# FPGA_Bank_3.net
KiCad netlist of a schematic drawn in Altium Designer
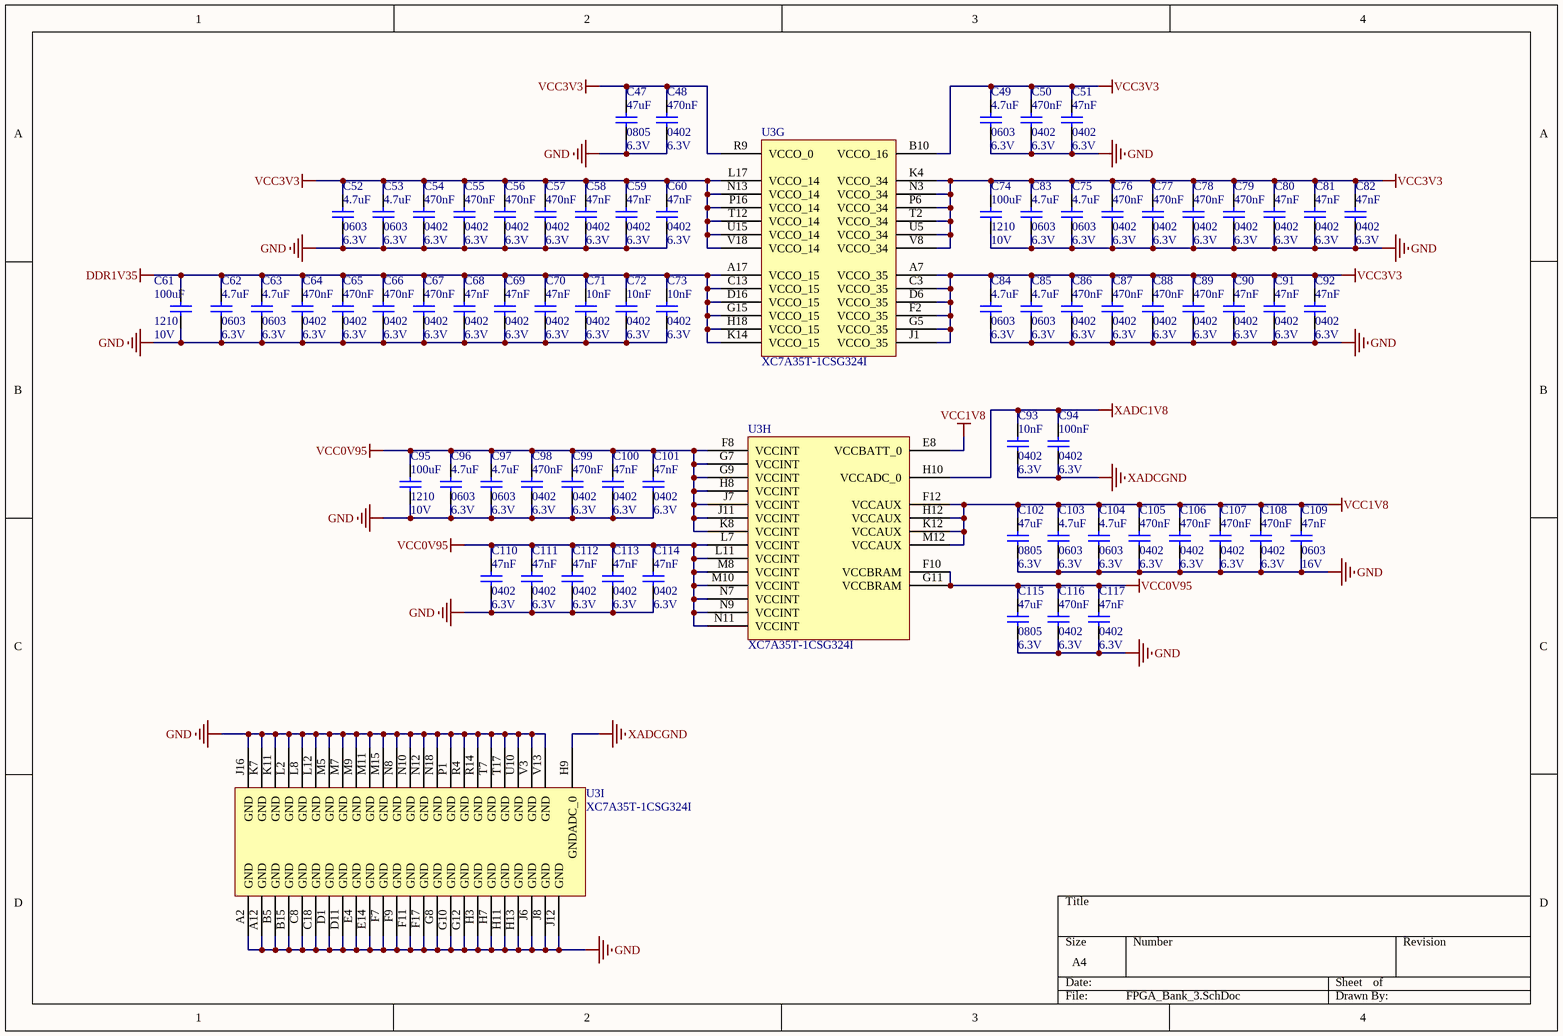
[diagram p0: FPGA_Bank_3.SchDoc]

(export (version "E")
  (design (tool "Eeschema 10.0.6"))
  (components
    (comp (ref "C47")
      (value "47uF")
      (footprint "2012[0805]")
      (description "Capacitor (Semiconductor SIM Model)")
      (fields
        (field (name "PACKAGEREFERENCE") "0805")
        (field (name "V") "6.3V")
        (field (name "PUBLISHER") "Altium Limited")
      )
      (libsource (lib "Devices") (part "Cap Semi"))
    )
    (comp (ref "C48")
      (value "470nF")
      (footprint "0402")
      (description "Capacitor (Semiconductor SIM Model)")
      (fields
        (field (name "PACKAGEREFERENCE") "0402")
        (field (name "V") "6.3V")
        (field (name "PUBLISHER") "Altium Limited")
      )
      (libsource (lib "Devices") (part "Cap Semi"))
    )
    (comp (ref "C49")
      (value "4.7uF")
      (footprint "1608[0603]")
      (description "Capacitor (Semiconductor SIM Model)")
      (fields
        (field (name "PACKAGEREFERENCE") "0603")
        (field (name "V") "6.3V")
        (field (name "PUBLISHER") "Altium Limited")
      )
      (libsource (lib "Devices") (part "Cap Semi"))
    )
    (comp (ref "C50")
      (value "470nF")
      (footprint "0402")
      (description "Capacitor (Semiconductor SIM Model)")
      (fields
        (field (name "PACKAGEREFERENCE") "0402")
        (field (name "V") "6.3V")
        (field (name "PUBLISHER") "Altium Limited")
      )
      (libsource (lib "Devices") (part "Cap Semi"))
    )
    (comp (ref "C51")
      (value "47nF")
      (footprint "0402")
      (description "Capacitor (Semiconductor SIM Model)")
      (fields
        (field (name "PACKAGEREFERENCE") "0402")
        (field (name "V") "6.3V")
        (field (name "PUBLISHER") "Altium Limited")
      )
      (libsource (lib "Devices") (part "Cap Semi"))
    )
    (comp (ref "C52")
      (value "4.7uF")
      (footprint "1608[0603]")
      (description "Capacitor (Semiconductor SIM Model)")
      (fields
        (field (name "PACKAGEREFERENCE") "0603")
        (field (name "V") "6.3V")
        (field (name "PUBLISHER") "Altium Limited")
      )
      (libsource (lib "Devices") (part "Cap Semi"))
    )
    (comp (ref "C53")
      (value "4.7uF")
      (footprint "1608[0603]")
      (description "Capacitor (Semiconductor SIM Model)")
      (fields
        (field (name "PACKAGEREFERENCE") "0603")
        (field (name "V") "6.3V")
        (field (name "PUBLISHER") "Altium Limited")
      )
      (libsource (lib "Devices") (part "Cap Semi"))
    )
    (comp (ref "C54")
      (value "470nF")
      (footprint "0402")
      (description "Capacitor (Semiconductor SIM Model)")
      (fields
        (field (name "PACKAGEREFERENCE") "0402")
        (field (name "V") "6.3V")
        (field (name "PUBLISHER") "Altium Limited")
      )
      (libsource (lib "Devices") (part "Cap Semi"))
    )
    (comp (ref "C55")
      (value "470nF")
      (footprint "0402")
      (description "Capacitor (Semiconductor SIM Model)")
      (fields
        (field (name "PACKAGEREFERENCE") "0402")
        (field (name "V") "6.3V")
        (field (name "PUBLISHER") "Altium Limited")
      )
      (libsource (lib "Devices") (part "Cap Semi"))
    )
    (comp (ref "C56")
      (value "470nF")
      (footprint "0402")
      (description "Capacitor (Semiconductor SIM Model)")
      (fields
        (field (name "PACKAGEREFERENCE") "0402")
        (field (name "V") "6.3V")
        (field (name "PUBLISHER") "Altium Limited")
      )
      (libsource (lib "Devices") (part "Cap Semi"))
    )
    (comp (ref "C57")
      (value "470nF")
      (footprint "0402")
      (description "Capacitor (Semiconductor SIM Model)")
      (fields
        (field (name "PACKAGEREFERENCE") "0402")
        (field (name "V") "6.3V")
        (field (name "PUBLISHER") "Altium Limited")
      )
      (libsource (lib "Devices") (part "Cap Semi"))
    )
    (comp (ref "C58")
      (value "47nF")
      (footprint "0402")
      (description "Capacitor (Semiconductor SIM Model)")
      (fields
        (field (name "PACKAGEREFERENCE") "0402")
        (field (name "V") "6.3V")
        (field (name "PUBLISHER") "Altium Limited")
      )
      (libsource (lib "Devices") (part "Cap Semi"))
    )
    (comp (ref "C59")
      (value "47nF")
      (footprint "0402")
      (description "Capacitor (Semiconductor SIM Model)")
      (fields
        (field (name "PACKAGEREFERENCE") "0402")
        (field (name "V") "6.3V")
        (field (name "PUBLISHER") "Altium Limited")
      )
      (libsource (lib "Devices") (part "Cap Semi"))
    )
    (comp (ref "C60")
      (value "47nF")
      (footprint "0402")
      (description "Capacitor (Semiconductor SIM Model)")
      (fields
        (field (name "PACKAGEREFERENCE") "0402")
        (field (name "V") "6.3V")
        (field (name "PUBLISHER") "Altium Limited")
      )
      (libsource (lib "Devices") (part "Cap Semi"))
    )
    (comp (ref "C61")
      (value "100uF")
      (footprint "2012[0805]")
      (description "Capacitor (Semiconductor SIM Model)")
      (fields
        (field (name "PACKAGEREFERENCE") "1210")
        (field (name "V") "10V")
        (field (name "PUBLISHER") "Altium Limited")
      )
      (libsource (lib "Devices") (part "Cap Semi"))
    )
    (comp (ref "C62")
      (value "4.7uF")
      (footprint "1608[0603]")
      (description "Capacitor (Semiconductor SIM Model)")
      (fields
        (field (name "PACKAGEREFERENCE") "0603")
        (field (name "V") "6.3V")
        (field (name "PUBLISHER") "Altium Limited")
      )
      (libsource (lib "Devices") (part "Cap Semi"))
    )
    (comp (ref "C63")
      (value "4.7uF")
      (footprint "1608[0603]")
      (description "Capacitor (Semiconductor SIM Model)")
      (fields
        (field (name "PACKAGEREFERENCE") "0603")
        (field (name "V") "6.3V")
        (field (name "PUBLISHER") "Altium Limited")
      )
      (libsource (lib "Devices") (part "Cap Semi"))
    )
    (comp (ref "C64")
      (value "470nF")
      (footprint "0402")
      (description "Capacitor (Semiconductor SIM Model)")
      (fields
        (field (name "PACKAGEREFERENCE") "0402")
        (field (name "V") "6.3V")
        (field (name "PUBLISHER") "Altium Limited")
      )
      (libsource (lib "Devices") (part "Cap Semi"))
    )
    (comp (ref "C65")
      (value "470nF")
      (footprint "0402")
      (description "Capacitor (Semiconductor SIM Model)")
      (fields
        (field (name "PACKAGEREFERENCE") "0402")
        (field (name "V") "6.3V")
        (field (name "PUBLISHER") "Altium Limited")
      )
      (libsource (lib "Devices") (part "Cap Semi"))
    )
    (comp (ref "C66")
      (value "470nF")
      (footprint "0402")
      (description "Capacitor (Semiconductor SIM Model)")
      (fields
        (field (name "PACKAGEREFERENCE") "0402")
        (field (name "V") "6.3V")
        (field (name "PUBLISHER") "Altium Limited")
      )
      (libsource (lib "Devices") (part "Cap Semi"))
    )
    (comp (ref "C67")
      (value "470nF")
      (footprint "0402")
      (description "Capacitor (Semiconductor SIM Model)")
      (fields
        (field (name "PACKAGEREFERENCE") "0402")
        (field (name "V") "6.3V")
        (field (name "PUBLISHER") "Altium Limited")
      )
      (libsource (lib "Devices") (part "Cap Semi"))
    )
    (comp (ref "C68")
      (value "47nF")
      (footprint "0402")
      (description "Capacitor (Semiconductor SIM Model)")
      (fields
        (field (name "PACKAGEREFERENCE") "0402")
        (field (name "V") "6.3V")
        (field (name "PUBLISHER") "Altium Limited")
      )
      (libsource (lib "Devices") (part "Cap Semi"))
    )
    (comp (ref "C69")
      (value "47nF")
      (footprint "0402")
      (description "Capacitor (Semiconductor SIM Model)")
      (fields
        (field (name "PACKAGEREFERENCE") "0402")
        (field (name "V") "6.3V")
        (field (name "PUBLISHER") "Altium Limited")
      )
      (libsource (lib "Devices") (part "Cap Semi"))
    )
    (comp (ref "C70")
      (value "47nF")
      (footprint "0402")
      (description "Capacitor (Semiconductor SIM Model)")
      (fields
        (field (name "PACKAGEREFERENCE") "0402")
        (field (name "V") "6.3V")
        (field (name "PUBLISHER") "Altium Limited")
      )
      (libsource (lib "Devices") (part "Cap Semi"))
    )
    (comp (ref "C71")
      (value "10nF")
      (footprint "0402")
      (description "Capacitor (Semiconductor SIM Model)")
      (fields
        (field (name "PACKAGEREFERENCE") "0402")
        (field (name "V") "6.3V")
        (field (name "PUBLISHER") "Altium Limited")
      )
      (libsource (lib "Devices") (part "Cap Semi"))
    )
    (comp (ref "C72")
      (value "10nF")
      (footprint "0402")
      (description "Capacitor (Semiconductor SIM Model)")
      (fields
        (field (name "PACKAGEREFERENCE") "0402")
        (field (name "V") "6.3V")
        (field (name "PUBLISHER") "Altium Limited")
      )
      (libsource (lib "Devices") (part "Cap Semi"))
    )
    (comp (ref "C73")
      (value "10nF")
      (footprint "0402")
      (description "Capacitor (Semiconductor SIM Model)")
      (fields
        (field (name "PACKAGEREFERENCE") "0402")
        (field (name "V") "6.3V")
        (field (name "PUBLISHER") "Altium Limited")
      )
      (libsource (lib "Devices") (part "Cap Semi"))
    )
    (comp (ref "C74")
      (value "100uF")
      (footprint "2012[0805]")
      (description "Capacitor (Semiconductor SIM Model)")
      (fields
        (field (name "PACKAGEREFERENCE") "1210")
        (field (name "V") "10V")
        (field (name "PUBLISHER") "Altium Limited")
      )
      (libsource (lib "Devices") (part "Cap Semi"))
    )
    (comp (ref "C75")
      (value "4.7uF")
      (footprint "1608[0603]")
      (description "Capacitor (Semiconductor SIM Model)")
      (fields
        (field (name "PACKAGEREFERENCE") "0603")
        (field (name "V") "6.3V")
        (field (name "PUBLISHER") "Altium Limited")
      )
      (libsource (lib "Devices") (part "Cap Semi"))
    )
    (comp (ref "C76")
      (value "470nF")
      (footprint "0402")
      (description "Capacitor (Semiconductor SIM Model)")
      (fields
        (field (name "PACKAGEREFERENCE") "0402")
        (field (name "V") "6.3V")
        (field (name "PUBLISHER") "Altium Limited")
      )
      (libsource (lib "Devices") (part "Cap Semi"))
    )
    (comp (ref "C77")
      (value "470nF")
      (footprint "0402")
      (description "Capacitor (Semiconductor SIM Model)")
      (fields
        (field (name "PACKAGEREFERENCE") "0402")
        (field (name "V") "6.3V")
        (field (name "PUBLISHER") "Altium Limited")
      )
      (libsource (lib "Devices") (part "Cap Semi"))
    )
    (comp (ref "C78")
      (value "470nF")
      (footprint "0402")
      (description "Capacitor (Semiconductor SIM Model)")
      (fields
        (field (name "PACKAGEREFERENCE") "0402")
        (field (name "V") "6.3V")
        (field (name "PUBLISHER") "Altium Limited")
      )
      (libsource (lib "Devices") (part "Cap Semi"))
    )
    (comp (ref "C79")
      (value "470nF")
      (footprint "0402")
      (description "Capacitor (Semiconductor SIM Model)")
      (fields
        (field (name "PACKAGEREFERENCE") "0402")
        (field (name "V") "6.3V")
        (field (name "PUBLISHER") "Altium Limited")
      )
      (libsource (lib "Devices") (part "Cap Semi"))
    )
    (comp (ref "C80")
      (value "47nF")
      (footprint "0402")
      (description "Capacitor (Semiconductor SIM Model)")
      (fields
        (field (name "PACKAGEREFERENCE") "0402")
        (field (name "V") "6.3V")
        (field (name "PUBLISHER") "Altium Limited")
      )
      (libsource (lib "Devices") (part "Cap Semi"))
    )
    (comp (ref "C81")
      (value "47nF")
      (footprint "0402")
      (description "Capacitor (Semiconductor SIM Model)")
      (fields
        (field (name "PACKAGEREFERENCE") "0402")
        (field (name "V") "6.3V")
        (field (name "PUBLISHER") "Altium Limited")
      )
      (libsource (lib "Devices") (part "Cap Semi"))
    )
    (comp (ref "C82")
      (value "47nF")
      (footprint "0402")
      (description "Capacitor (Semiconductor SIM Model)")
      (fields
        (field (name "PACKAGEREFERENCE") "0402")
        (field (name "V") "6.3V")
        (field (name "PUBLISHER") "Altium Limited")
      )
      (libsource (lib "Devices") (part "Cap Semi"))
    )
    (comp (ref "C83")
      (value "4.7uF")
      (footprint "1608[0603]")
      (description "Capacitor (Semiconductor SIM Model)")
      (fields
        (field (name "PACKAGEREFERENCE") "0603")
        (field (name "V") "6.3V")
        (field (name "PUBLISHER") "Altium Limited")
      )
      (libsource (lib "Devices") (part "Cap Semi"))
    )
    (comp (ref "C84")
      (value "4.7uF")
      (footprint "1608[0603]")
      (description "Capacitor (Semiconductor SIM Model)")
      (fields
        (field (name "PACKAGEREFERENCE") "0603")
        (field (name "V") "6.3V")
        (field (name "PUBLISHER") "Altium Limited")
      )
      (libsource (lib "Devices") (part "Cap Semi"))
    )
    (comp (ref "C85")
      (value "4.7uF")
      (footprint "1608[0603]")
      (description "Capacitor (Semiconductor SIM Model)")
      (fields
        (field (name "PACKAGEREFERENCE") "0603")
        (field (name "V") "6.3V")
        (field (name "PUBLISHER") "Altium Limited")
      )
      (libsource (lib "Devices") (part "Cap Semi"))
    )
    (comp (ref "C86")
      (value "470nF")
      (footprint "0402")
      (description "Capacitor (Semiconductor SIM Model)")
      (fields
        (field (name "PACKAGEREFERENCE") "0402")
        (field (name "V") "6.3V")
        (field (name "PUBLISHER") "Altium Limited")
      )
      (libsource (lib "Devices") (part "Cap Semi"))
    )
    (comp (ref "C87")
      (value "470nF")
      (footprint "0402")
      (description "Capacitor (Semiconductor SIM Model)")
      (fields
        (field (name "PACKAGEREFERENCE") "0402")
        (field (name "V") "6.3V")
        (field (name "PUBLISHER") "Altium Limited")
      )
      (libsource (lib "Devices") (part "Cap Semi"))
    )
    (comp (ref "C88")
      (value "470nF")
      (footprint "0402")
      (description "Capacitor (Semiconductor SIM Model)")
      (fields
        (field (name "PACKAGEREFERENCE") "0402")
        (field (name "V") "6.3V")
        (field (name "PUBLISHER") "Altium Limited")
      )
      (libsource (lib "Devices") (part "Cap Semi"))
    )
    (comp (ref "C89")
      (value "470nF")
      (footprint "0402")
      (description "Capacitor (Semiconductor SIM Model)")
      (fields
        (field (name "PACKAGEREFERENCE") "0402")
        (field (name "V") "6.3V")
        (field (name "PUBLISHER") "Altium Limited")
      )
      (libsource (lib "Devices") (part "Cap Semi"))
    )
    (comp (ref "C90")
      (value "47nF")
      (footprint "0402")
      (description "Capacitor (Semiconductor SIM Model)")
      (fields
        (field (name "PACKAGEREFERENCE") "0402")
        (field (name "V") "6.3V")
        (field (name "PUBLISHER") "Altium Limited")
      )
      (libsource (lib "Devices") (part "Cap Semi"))
    )
    (comp (ref "C91")
      (value "47nF")
      (footprint "0402")
      (description "Capacitor (Semiconductor SIM Model)")
      (fields
        (field (name "PACKAGEREFERENCE") "0402")
        (field (name "V") "6.3V")
        (field (name "PUBLISHER") "Altium Limited")
      )
      (libsource (lib "Devices") (part "Cap Semi"))
    )
    (comp (ref "C92")
      (value "47nF")
      (footprint "0402")
      (description "Capacitor (Semiconductor SIM Model)")
      (fields
        (field (name "PACKAGEREFERENCE") "0402")
        (field (name "V") "6.3V")
        (field (name "PUBLISHER") "Altium Limited")
      )
      (libsource (lib "Devices") (part "Cap Semi"))
    )
    (comp (ref "C93")
      (value "10nF")
      (footprint "0402")
      (description "Capacitor (Semiconductor SIM Model)")
      (fields
        (field (name "PACKAGEREFERENCE") "0402")
        (field (name "V") "6.3V")
        (field (name "PUBLISHER") "Altium Limited")
      )
      (libsource (lib "Devices") (part "Cap Semi"))
    )
    (comp (ref "C94")
      (value "100nF")
      (footprint "0402")
      (description "Capacitor (Semiconductor SIM Model)")
      (fields
        (field (name "PACKAGEREFERENCE") "0402")
        (field (name "V") "6.3V")
        (field (name "PUBLISHER") "Altium Limited")
      )
      (libsource (lib "Devices") (part "Cap Semi"))
    )
    (comp (ref "C95")
      (value "100uF")
      (footprint "2012[0805]")
      (description "Capacitor (Semiconductor SIM Model)")
      (fields
        (field (name "PACKAGEREFERENCE") "1210")
        (field (name "V") "10V")
        (field (name "PUBLISHER") "Altium Limited")
      )
      (libsource (lib "Devices") (part "Cap Semi"))
    )
    (comp (ref "C96")
      (value "4.7uF")
      (footprint "1608[0603]")
      (description "Capacitor (Semiconductor SIM Model)")
      (fields
        (field (name "PACKAGEREFERENCE") "0603")
        (field (name "V") "6.3V")
        (field (name "PUBLISHER") "Altium Limited")
      )
      (libsource (lib "Devices") (part "Cap Semi"))
    )
    (comp (ref "C97")
      (value "4.7uF")
      (footprint "1608[0603]")
      (description "Capacitor (Semiconductor SIM Model)")
      (fields
        (field (name "PACKAGEREFERENCE") "0603")
        (field (name "V") "6.3V")
        (field (name "PUBLISHER") "Altium Limited")
      )
      (libsource (lib "Devices") (part "Cap Semi"))
    )
    (comp (ref "C98")
      (value "470nF")
      (footprint "0402")
      (description "Capacitor (Semiconductor SIM Model)")
      (fields
        (field (name "PACKAGEREFERENCE") "0402")
        (field (name "V") "6.3V")
        (field (name "PUBLISHER") "Altium Limited")
      )
      (libsource (lib "Devices") (part "Cap Semi"))
    )
    (comp (ref "C99")
      (value "470nF")
      (footprint "0402")
      (description "Capacitor (Semiconductor SIM Model)")
      (fields
        (field (name "PACKAGEREFERENCE") "0402")
        (field (name "V") "6.3V")
        (field (name "PUBLISHER") "Altium Limited")
      )
      (libsource (lib "Devices") (part "Cap Semi"))
    )
    (comp (ref "C100")
      (value "47nF")
      (footprint "0402")
      (description "Capacitor (Semiconductor SIM Model)")
      (fields
        (field (name "PACKAGEREFERENCE") "0402")
        (field (name "V") "6.3V")
        (field (name "PUBLISHER") "Altium Limited")
      )
      (libsource (lib "Devices") (part "Cap Semi"))
    )
    (comp (ref "C101")
      (value "47nF")
      (footprint "0402")
      (description "Capacitor (Semiconductor SIM Model)")
      (fields
        (field (name "PACKAGEREFERENCE") "0402")
        (field (name "V") "6.3V")
        (field (name "PUBLISHER") "Altium Limited")
      )
      (libsource (lib "Devices") (part "Cap Semi"))
    )
    (comp (ref "C102")
      (value "47uF")
      (footprint "2012[0805]")
      (description "Capacitor (Semiconductor SIM Model)")
      (fields
        (field (name "PACKAGEREFERENCE") "0805")
        (field (name "V") "6.3V")
        (field (name "PUBLISHER") "Altium Limited")
      )
      (libsource (lib "Devices") (part "Cap Semi"))
    )
    (comp (ref "C103")
      (value "4.7uF")
      (footprint "1608[0603]")
      (description "Capacitor (Semiconductor SIM Model)")
      (fields
        (field (name "PACKAGEREFERENCE") "0603")
        (field (name "V") "6.3V")
        (field (name "PUBLISHER") "Altium Limited")
      )
      (libsource (lib "Devices") (part "Cap Semi"))
    )
    (comp (ref "C104")
      (value "4.7uF")
      (footprint "1608[0603]")
      (description "Capacitor (Semiconductor SIM Model)")
      (fields
        (field (name "PACKAGEREFERENCE") "0603")
        (field (name "V") "6.3V")
        (field (name "PUBLISHER") "Altium Limited")
      )
      (libsource (lib "Devices") (part "Cap Semi"))
    )
    (comp (ref "C105")
      (value "470nF")
      (footprint "0402")
      (description "Capacitor (Semiconductor SIM Model)")
      (fields
        (field (name "PACKAGEREFERENCE") "0402")
        (field (name "V") "6.3V")
        (field (name "PUBLISHER") "Altium Limited")
      )
      (libsource (lib "Devices") (part "Cap Semi"))
    )
    (comp (ref "C106")
      (value "470nF")
      (footprint "0402")
      (description "Capacitor (Semiconductor SIM Model)")
      (fields
        (field (name "PACKAGEREFERENCE") "0402")
        (field (name "V") "6.3V")
        (field (name "PUBLISHER") "Altium Limited")
      )
      (libsource (lib "Devices") (part "Cap Semi"))
    )
    (comp (ref "C107")
      (value "470nF")
      (footprint "0402")
      (description "Capacitor (Semiconductor SIM Model)")
      (fields
        (field (name "PACKAGEREFERENCE") "0402")
        (field (name "V") "6.3V")
        (field (name "PUBLISHER") "Altium Limited")
      )
      (libsource (lib "Devices") (part "Cap Semi"))
    )
    (comp (ref "C108")
      (value "470nF")
      (footprint "0402")
      (description "Capacitor (Semiconductor SIM Model)")
      (fields
        (field (name "PACKAGEREFERENCE") "0402")
        (field (name "V") "6.3V")
        (field (name "PUBLISHER") "Altium Limited")
      )
      (libsource (lib "Devices") (part "Cap Semi"))
    )
    (comp (ref "C109")
      (value "47nF")
      (footprint "1608[0603]")
      (description "Capacitor (Semiconductor SIM Model)")
      (fields
        (field (name "PACKAGEREFERENCE") "0603")
        (field (name "V") "16V")
        (field (name "PUBLISHER") "Altium Limited")
      )
      (libsource (lib "Devices") (part "Cap Semi"))
    )
    (comp (ref "C110")
      (value "47nF")
      (footprint "0402")
      (description "Capacitor (Semiconductor SIM Model)")
      (fields
        (field (name "PACKAGEREFERENCE") "0402")
        (field (name "V") "6.3V")
        (field (name "PUBLISHER") "Altium Limited")
      )
      (libsource (lib "Devices") (part "Cap Semi"))
    )
    (comp (ref "C111")
      (value "47nF")
      (footprint "0402")
      (description "Capacitor (Semiconductor SIM Model)")
      (fields
        (field (name "PACKAGEREFERENCE") "0402")
        (field (name "V") "6.3V")
        (field (name "PUBLISHER") "Altium Limited")
      )
      (libsource (lib "Devices") (part "Cap Semi"))
    )
    (comp (ref "C112")
      (value "47nF")
      (footprint "0402")
      (description "Capacitor (Semiconductor SIM Model)")
      (fields
        (field (name "PACKAGEREFERENCE") "0402")
        (field (name "V") "6.3V")
        (field (name "PUBLISHER") "Altium Limited")
      )
      (libsource (lib "Devices") (part "Cap Semi"))
    )
    (comp (ref "C113")
      (value "47nF")
      (footprint "0402")
      (description "Capacitor (Semiconductor SIM Model)")
      (fields
        (field (name "PACKAGEREFERENCE") "0402")
        (field (name "V") "6.3V")
        (field (name "PUBLISHER") "Altium Limited")
      )
      (libsource (lib "Devices") (part "Cap Semi"))
    )
    (comp (ref "C114")
      (value "47nF")
      (footprint "0402")
      (description "Capacitor (Semiconductor SIM Model)")
      (fields
        (field (name "PACKAGEREFERENCE") "0402")
        (field (name "V") "6.3V")
        (field (name "PUBLISHER") "Altium Limited")
      )
      (libsource (lib "Devices") (part "Cap Semi"))
    )
    (comp (ref "C115")
      (value "47uF")
      (footprint "2012[0805]")
      (description "Capacitor (Semiconductor SIM Model)")
      (fields
        (field (name "PACKAGEREFERENCE") "0805")
        (field (name "V") "6.3V")
        (field (name "PUBLISHER") "Altium Limited")
      )
      (libsource (lib "Devices") (part "Cap Semi"))
    )
    (comp (ref "C116")
      (value "470nF")
      (footprint "0402")
      (description "Capacitor (Semiconductor SIM Model)")
      (fields
        (field (name "PACKAGEREFERENCE") "0402")
        (field (name "V") "6.3V")
        (field (name "PUBLISHER") "Altium Limited")
      )
      (libsource (lib "Devices") (part "Cap Semi"))
    )
    (comp (ref "C117")
      (value "47nF")
      (footprint "0402")
      (description "Capacitor (Semiconductor SIM Model)")
      (fields
        (field (name "PACKAGEREFERENCE") "0402")
        (field (name "V") "6.3V")
        (field (name "PUBLISHER") "Altium Limited")
      )
      (libsource (lib "Devices") (part "Cap Semi"))
    )
    (comp (ref "U3")
      (value "XC7A35T-1CSG324I")
      (footprint "CSG324")
      (description "Artix-7 FPGA, 210 User I/Os, 0 GTP, 324-Ball BGA, Speed Grade 1, Industrial Grade, Pb-Free")
      (fields (field (name "MANUFACTURER") "Xilinx"))
      (libsource (lib "Xilinx Artix-7") (part "XC7A35T-1CSG324I"))
    )
  )
  (nets
    (net (code "1") (name "DDR1V35") (class "Default")
      (node (ref "C61") (pin "1") (pinfunction "1_1") (pintype "passive"))
      (node (ref "C62") (pin "1") (pinfunction "1_1") (pintype "passive"))
      (node (ref "C63") (pin "1") (pinfunction "1_1") (pintype "passive"))
      (node (ref "C64") (pin "1") (pinfunction "1_1") (pintype "passive"))
      (node (ref "C65") (pin "1") (pinfunction "1_1") (pintype "passive"))
      (node (ref "C66") (pin "1") (pinfunction "1_1") (pintype "passive"))
      (node (ref "C67") (pin "1") (pinfunction "1_1") (pintype "passive"))
      (node (ref "C68") (pin "1") (pinfunction "1_1") (pintype "passive"))
      (node (ref "C69") (pin "1") (pinfunction "1_1") (pintype "passive"))
      (node (ref "C70") (pin "1") (pinfunction "1_1") (pintype "passive"))
      (node (ref "C71") (pin "1") (pinfunction "1_1") (pintype "passive"))
      (node (ref "C72") (pin "1") (pinfunction "1_1") (pintype "passive"))
      (node (ref "C73") (pin "1") (pinfunction "1_1") (pintype "passive"))
      (node (ref "U3") (pin "A17") (pinfunction "VCCO_15_A17") (pintype "power_in"))
      (node (ref "U3") (pin "C13") (pinfunction "VCCO_15_C13") (pintype "power_in"))
      (node (ref "U3") (pin "D16") (pinfunction "VCCO_15_D16") (pintype "power_in"))
      (node (ref "U3") (pin "G15") (pinfunction "VCCO_15_G15") (pintype "power_in"))
      (node (ref "U3") (pin "H18") (pinfunction "VCCO_15_H18") (pintype "power_in"))
      (node (ref "U3") (pin "K14") (pinfunction "VCCO_15_K14") (pintype "power_in"))
    )
    (net (code "2") (name "GND") (class "Default")
      (node (ref "C100") (pin "2") (pinfunction "2_2") (pintype "passive"))
      (node (ref "C101") (pin "2") (pinfunction "2_2") (pintype "passive"))
      (node (ref "C102") (pin "2") (pinfunction "2_2") (pintype "passive"))
      (node (ref "C103") (pin "2") (pinfunction "2_2") (pintype "passive"))
      (node (ref "C104") (pin "2") (pinfunction "2_2") (pintype "passive"))
      (node (ref "C105") (pin "2") (pinfunction "2_2") (pintype "passive"))
      (node (ref "C106") (pin "2") (pinfunction "2_2") (pintype "passive"))
      (node (ref "C107") (pin "2") (pinfunction "2_2") (pintype "passive"))
      (node (ref "C108") (pin "2") (pinfunction "2_2") (pintype "passive"))
      (node (ref "C109") (pin "2") (pinfunction "2_2") (pintype "passive"))
      (node (ref "C110") (pin "2") (pinfunction "2_2") (pintype "passive"))
      (node (ref "C111") (pin "2") (pinfunction "2_2") (pintype "passive"))
      (node (ref "C112") (pin "2") (pinfunction "2_2") (pintype "passive"))
      (node (ref "C113") (pin "2") (pinfunction "2_2") (pintype "passive"))
      (node (ref "C114") (pin "2") (pinfunction "2_2") (pintype "passive"))
      (node (ref "C115") (pin "2") (pinfunction "2_2") (pintype "passive"))
      (node (ref "C116") (pin "2") (pinfunction "2_2") (pintype "passive"))
      (node (ref "C117") (pin "2") (pinfunction "2_2") (pintype "passive"))
      (node (ref "C47") (pin "2") (pinfunction "2_2") (pintype "passive"))
      (node (ref "C48") (pin "2") (pinfunction "2_2") (pintype "passive"))
      (node (ref "C49") (pin "2") (pinfunction "2_2") (pintype "passive"))
      (node (ref "C50") (pin "2") (pinfunction "2_2") (pintype "passive"))
      (node (ref "C51") (pin "2") (pinfunction "2_2") (pintype "passive"))
      (node (ref "C52") (pin "2") (pinfunction "2_2") (pintype "passive"))
      (node (ref "C53") (pin "2") (pinfunction "2_2") (pintype "passive"))
      (node (ref "C54") (pin "2") (pinfunction "2_2") (pintype "passive"))
      (node (ref "C55") (pin "2") (pinfunction "2_2") (pintype "passive"))
      (node (ref "C56") (pin "2") (pinfunction "2_2") (pintype "passive"))
      (node (ref "C57") (pin "2") (pinfunction "2_2") (pintype "passive"))
      (node (ref "C58") (pin "2") (pinfunction "2_2") (pintype "passive"))
      (node (ref "C59") (pin "2") (pinfunction "2_2") (pintype "passive"))
      (node (ref "C60") (pin "2") (pinfunction "2_2") (pintype "passive"))
      (node (ref "C61") (pin "2") (pinfunction "2_2") (pintype "passive"))
      (node (ref "C62") (pin "2") (pinfunction "2_2") (pintype "passive"))
      (node (ref "C63") (pin "2") (pinfunction "2_2") (pintype "passive"))
      (node (ref "C64") (pin "2") (pinfunction "2_2") (pintype "passive"))
      (node (ref "C65") (pin "2") (pinfunction "2_2") (pintype "passive"))
      (node (ref "C66") (pin "2") (pinfunction "2_2") (pintype "passive"))
      (node (ref "C67") (pin "2") (pinfunction "2_2") (pintype "passive"))
      (node (ref "C68") (pin "2") (pinfunction "2_2") (pintype "passive"))
      (node (ref "C69") (pin "2") (pinfunction "2_2") (pintype "passive"))
      (node (ref "C70") (pin "2") (pinfunction "2_2") (pintype "passive"))
      (node (ref "C71") (pin "2") (pinfunction "2_2") (pintype "passive"))
      (node (ref "C72") (pin "2") (pinfunction "2_2") (pintype "passive"))
      (node (ref "C73") (pin "2") (pinfunction "2_2") (pintype "passive"))
      (node (ref "C74") (pin "2") (pinfunction "2_2") (pintype "passive"))
      (node (ref "C75") (pin "2") (pinfunction "2_2") (pintype "passive"))
      (node (ref "C76") (pin "2") (pinfunction "2_2") (pintype "passive"))
      (node (ref "C77") (pin "2") (pinfunction "2_2") (pintype "passive"))
      (node (ref "C78") (pin "2") (pinfunction "2_2") (pintype "passive"))
      (node (ref "C79") (pin "2") (pinfunction "2_2") (pintype "passive"))
      (node (ref "C80") (pin "2") (pinfunction "2_2") (pintype "passive"))
      (node (ref "C81") (pin "2") (pinfunction "2_2") (pintype "passive"))
      (node (ref "C82") (pin "2") (pinfunction "2_2") (pintype "passive"))
      (node (ref "C83") (pin "2") (pinfunction "2_2") (pintype "passive"))
      (node (ref "C84") (pin "2") (pinfunction "2_2") (pintype "passive"))
      (node (ref "C85") (pin "2") (pinfunction "2_2") (pintype "passive"))
      (node (ref "C86") (pin "2") (pinfunction "2_2") (pintype "passive"))
      (node (ref "C87") (pin "2") (pinfunction "2_2") (pintype "passive"))
      (node (ref "C88") (pin "2") (pinfunction "2_2") (pintype "passive"))
      (node (ref "C89") (pin "2") (pinfunction "2_2") (pintype "passive"))
      (node (ref "C90") (pin "2") (pinfunction "2_2") (pintype "passive"))
      (node (ref "C91") (pin "2") (pinfunction "2_2") (pintype "passive"))
      (node (ref "C92") (pin "2") (pinfunction "2_2") (pintype "passive"))
      (node (ref "C95") (pin "2") (pinfunction "2_2") (pintype "passive"))
      (node (ref "C96") (pin "2") (pinfunction "2_2") (pintype "passive"))
      (node (ref "C97") (pin "2") (pinfunction "2_2") (pintype "passive"))
      (node (ref "C98") (pin "2") (pinfunction "2_2") (pintype "passive"))
      (node (ref "C99") (pin "2") (pinfunction "2_2") (pintype "passive"))
      (node (ref "U3") (pin "A12") (pinfunction "GND_A12") (pintype "power_in"))
      (node (ref "U3") (pin "A2") (pinfunction "GND_A2") (pintype "power_in"))
      (node (ref "U3") (pin "B15") (pinfunction "GND_B15") (pintype "power_in"))
      (node (ref "U3") (pin "B5") (pinfunction "GND_B5") (pintype "power_in"))
      (node (ref "U3") (pin "C18") (pinfunction "GND_C18") (pintype "power_in"))
      (node (ref "U3") (pin "C8") (pinfunction "GND_C8") (pintype "power_in"))
      (node (ref "U3") (pin "D1") (pinfunction "GND_D1") (pintype "power_in"))
      (node (ref "U3") (pin "D11") (pinfunction "GND_D11") (pintype "power_in"))
      (node (ref "U3") (pin "E14") (pinfunction "GND_E14") (pintype "power_in"))
      (node (ref "U3") (pin "E4") (pinfunction "GND_E4") (pintype "power_in"))
      (node (ref "U3") (pin "F11") (pinfunction "GND_F11") (pintype "power_in"))
      (node (ref "U3") (pin "F17") (pinfunction "GND_F17") (pintype "power_in"))
      (node (ref "U3") (pin "F7") (pinfunction "GND_F7") (pintype "power_in"))
      (node (ref "U3") (pin "F9") (pinfunction "GND_F9") (pintype "power_in"))
      (node (ref "U3") (pin "G10") (pinfunction "GND_G10") (pintype "power_in"))
      (node (ref "U3") (pin "G12") (pinfunction "GND_G12") (pintype "power_in"))
      (node (ref "U3") (pin "G8") (pinfunction "GND_G8") (pintype "power_in"))
      (node (ref "U3") (pin "H11") (pinfunction "GND_H11") (pintype "power_in"))
      (node (ref "U3") (pin "H13") (pinfunction "GND_H13") (pintype "power_in"))
      (node (ref "U3") (pin "H3") (pinfunction "GND_H3") (pintype "power_in"))
      (node (ref "U3") (pin "H7") (pinfunction "GND_H7") (pintype "power_in"))
      (node (ref "U3") (pin "J12") (pinfunction "GND_J12") (pintype "power_in"))
      (node (ref "U3") (pin "J16") (pinfunction "GND_J16") (pintype "power_in"))
      (node (ref "U3") (pin "J6") (pinfunction "GND_J6") (pintype "power_in"))
      (node (ref "U3") (pin "J8") (pinfunction "GND_J8") (pintype "power_in"))
      (node (ref "U3") (pin "K11") (pinfunction "GND_K11") (pintype "power_in"))
      (node (ref "U3") (pin "K7") (pinfunction "GND_K7") (pintype "power_in"))
      (node (ref "U3") (pin "L12") (pinfunction "GND_L12") (pintype "power_in"))
      (node (ref "U3") (pin "L2") (pinfunction "GND_L2") (pintype "power_in"))
      (node (ref "U3") (pin "L8") (pinfunction "GND_L8") (pintype "power_in"))
      (node (ref "U3") (pin "M11") (pinfunction "GND_M11") (pintype "power_in"))
      (node (ref "U3") (pin "M15") (pinfunction "GND_M15") (pintype "power_in"))
      (node (ref "U3") (pin "M5") (pinfunction "GND_M5") (pintype "power_in"))
      (node (ref "U3") (pin "M7") (pinfunction "GND_M7") (pintype "power_in"))
      (node (ref "U3") (pin "M9") (pinfunction "GND_M9") (pintype "power_in"))
      (node (ref "U3") (pin "N10") (pinfunction "GND_N10") (pintype "power_in"))
      (node (ref "U3") (pin "N12") (pinfunction "GND_N12") (pintype "power_in"))
      (node (ref "U3") (pin "N18") (pinfunction "GND_N18") (pintype "power_in"))
      (node (ref "U3") (pin "N8") (pinfunction "GND_N8") (pintype "power_in"))
      (node (ref "U3") (pin "P1") (pinfunction "GND_P1") (pintype "power_in"))
      (node (ref "U3") (pin "R14") (pinfunction "GND_R14") (pintype "power_in"))
      (node (ref "U3") (pin "R4") (pinfunction "GND_R4") (pintype "power_in"))
      (node (ref "U3") (pin "T17") (pinfunction "GND_T17") (pintype "power_in"))
      (node (ref "U3") (pin "T7") (pinfunction "GND_T7") (pintype "power_in"))
      (node (ref "U3") (pin "U10") (pinfunction "GND_U10") (pintype "power_in"))
      (node (ref "U3") (pin "V13") (pinfunction "GND_V13") (pintype "power_in"))
      (node (ref "U3") (pin "V3") (pinfunction "GND_V3") (pintype "power_in"))
    )
    (net (code "3") (name "VCC0V95") (class "Default")
      (node (ref "C100") (pin "1") (pinfunction "1_1") (pintype "passive"))
      (node (ref "C101") (pin "1") (pinfunction "1_1") (pintype "passive"))
      (node (ref "C110") (pin "1") (pinfunction "1_1") (pintype "passive"))
      (node (ref "C111") (pin "1") (pinfunction "1_1") (pintype "passive"))
      (node (ref "C112") (pin "1") (pinfunction "1_1") (pintype "passive"))
      (node (ref "C113") (pin "1") (pinfunction "1_1") (pintype "passive"))
      (node (ref "C114") (pin "1") (pinfunction "1_1") (pintype "passive"))
      (node (ref "C115") (pin "1") (pinfunction "1_1") (pintype "passive"))
      (node (ref "C116") (pin "1") (pinfunction "1_1") (pintype "passive"))
      (node (ref "C117") (pin "1") (pinfunction "1_1") (pintype "passive"))
      (node (ref "C95") (pin "1") (pinfunction "1_1") (pintype "passive"))
      (node (ref "C96") (pin "1") (pinfunction "1_1") (pintype "passive"))
      (node (ref "C97") (pin "1") (pinfunction "1_1") (pintype "passive"))
      (node (ref "C98") (pin "1") (pinfunction "1_1") (pintype "passive"))
      (node (ref "C99") (pin "1") (pinfunction "1_1") (pintype "passive"))
      (node (ref "U3") (pin "F10") (pinfunction "VCCBRAM_F10") (pintype "power_in"))
      (node (ref "U3") (pin "F8") (pinfunction "VCCINT_F8") (pintype "power_in"))
      (node (ref "U3") (pin "G11") (pinfunction "VCCBRAM_G11") (pintype "power_in"))
      (node (ref "U3") (pin "G7") (pinfunction "VCCINT_G7") (pintype "power_in"))
      (node (ref "U3") (pin "G9") (pinfunction "VCCINT_G9") (pintype "power_in"))
      (node (ref "U3") (pin "H8") (pinfunction "VCCINT_H8") (pintype "power_in"))
      (node (ref "U3") (pin "J11") (pinfunction "VCCINT_J11") (pintype "power_in"))
      (node (ref "U3") (pin "J7") (pinfunction "VCCINT_J7") (pintype "power_in"))
      (node (ref "U3") (pin "K8") (pinfunction "VCCINT_K8") (pintype "power_in"))
      (node (ref "U3") (pin "L11") (pinfunction "VCCINT_L11") (pintype "power_in"))
      (node (ref "U3") (pin "L7") (pinfunction "VCCINT_L7") (pintype "power_in"))
      (node (ref "U3") (pin "M10") (pinfunction "VCCINT_M10") (pintype "power_in"))
      (node (ref "U3") (pin "M8") (pinfunction "VCCINT_M8") (pintype "power_in"))
      (node (ref "U3") (pin "N11") (pinfunction "VCCINT_N11") (pintype "power_in"))
      (node (ref "U3") (pin "N7") (pinfunction "VCCINT_N7") (pintype "power_in"))
      (node (ref "U3") (pin "N9") (pinfunction "VCCINT_N9") (pintype "power_in"))
    )
    (net (code "4") (name "VCC1V8") (class "Default")
      (node (ref "C102") (pin "1") (pinfunction "1_1") (pintype "passive"))
      (node (ref "C103") (pin "1") (pinfunction "1_1") (pintype "passive"))
      (node (ref "C104") (pin "1") (pinfunction "1_1") (pintype "passive"))
      (node (ref "C105") (pin "1") (pinfunction "1_1") (pintype "passive"))
      (node (ref "C106") (pin "1") (pinfunction "1_1") (pintype "passive"))
      (node (ref "C107") (pin "1") (pinfunction "1_1") (pintype "passive"))
      (node (ref "C108") (pin "1") (pinfunction "1_1") (pintype "passive"))
      (node (ref "C109") (pin "1") (pinfunction "1_1") (pintype "passive"))
      (node (ref "U3") (pin "E8") (pinfunction "VCCBATT_0_E8") (pintype "power_in"))
      (node (ref "U3") (pin "F12") (pinfunction "VCCAUX_F12") (pintype "power_in"))
      (node (ref "U3") (pin "H12") (pinfunction "VCCAUX_H12") (pintype "power_in"))
      (node (ref "U3") (pin "K12") (pinfunction "VCCAUX_K12") (pintype "power_in"))
      (node (ref "U3") (pin "M12") (pinfunction "VCCAUX_M12") (pintype "power_in"))
    )
    (net (code "5") (name "VCC3V3") (class "Default")
      (node (ref "C47") (pin "1") (pinfunction "1_1") (pintype "passive"))
      (node (ref "C48") (pin "1") (pinfunction "1_1") (pintype "passive"))
      (node (ref "C49") (pin "1") (pinfunction "1_1") (pintype "passive"))
      (node (ref "C50") (pin "1") (pinfunction "1_1") (pintype "passive"))
      (node (ref "C51") (pin "1") (pinfunction "1_1") (pintype "passive"))
      (node (ref "C52") (pin "1") (pinfunction "1_1") (pintype "passive"))
      (node (ref "C53") (pin "1") (pinfunction "1_1") (pintype "passive"))
      (node (ref "C54") (pin "1") (pinfunction "1_1") (pintype "passive"))
      (node (ref "C55") (pin "1") (pinfunction "1_1") (pintype "passive"))
      (node (ref "C56") (pin "1") (pinfunction "1_1") (pintype "passive"))
      (node (ref "C57") (pin "1") (pinfunction "1_1") (pintype "passive"))
      (node (ref "C58") (pin "1") (pinfunction "1_1") (pintype "passive"))
      (node (ref "C59") (pin "1") (pinfunction "1_1") (pintype "passive"))
      (node (ref "C60") (pin "1") (pinfunction "1_1") (pintype "passive"))
      (node (ref "C74") (pin "1") (pinfunction "1_1") (pintype "passive"))
      (node (ref "C75") (pin "1") (pinfunction "1_1") (pintype "passive"))
      (node (ref "C76") (pin "1") (pinfunction "1_1") (pintype "passive"))
      (node (ref "C77") (pin "1") (pinfunction "1_1") (pintype "passive"))
      (node (ref "C78") (pin "1") (pinfunction "1_1") (pintype "passive"))
      (node (ref "C79") (pin "1") (pinfunction "1_1") (pintype "passive"))
      (node (ref "C80") (pin "1") (pinfunction "1_1") (pintype "passive"))
      (node (ref "C81") (pin "1") (pinfunction "1_1") (pintype "passive"))
      (node (ref "C82") (pin "1") (pinfunction "1_1") (pintype "passive"))
      (node (ref "C83") (pin "1") (pinfunction "1_1") (pintype "passive"))
      (node (ref "C84") (pin "1") (pinfunction "1_1") (pintype "passive"))
      (node (ref "C85") (pin "1") (pinfunction "1_1") (pintype "passive"))
      (node (ref "C86") (pin "1") (pinfunction "1_1") (pintype "passive"))
      (node (ref "C87") (pin "1") (pinfunction "1_1") (pintype "passive"))
      (node (ref "C88") (pin "1") (pinfunction "1_1") (pintype "passive"))
      (node (ref "C89") (pin "1") (pinfunction "1_1") (pintype "passive"))
      (node (ref "C90") (pin "1") (pinfunction "1_1") (pintype "passive"))
      (node (ref "C91") (pin "1") (pinfunction "1_1") (pintype "passive"))
      (node (ref "C92") (pin "1") (pinfunction "1_1") (pintype "passive"))
      (node (ref "U3") (pin "A7") (pinfunction "VCCO_35_A7") (pintype "power_in"))
      (node (ref "U3") (pin "B10") (pinfunction "VCCO_16_B10") (pintype "power_in"))
      (node (ref "U3") (pin "C3") (pinfunction "VCCO_35_C3") (pintype "power_in"))
      (node (ref "U3") (pin "D6") (pinfunction "VCCO_35_D6") (pintype "power_in"))
      (node (ref "U3") (pin "F2") (pinfunction "VCCO_35_F2") (pintype "power_in"))
      (node (ref "U3") (pin "G5") (pinfunction "VCCO_35_G5") (pintype "power_in"))
      (node (ref "U3") (pin "J1") (pinfunction "VCCO_35_J1") (pintype "power_in"))
      (node (ref "U3") (pin "K4") (pinfunction "VCCO_34_K4") (pintype "power_in"))
      (node (ref "U3") (pin "L17") (pinfunction "VCCO_14_L17") (pintype "power_in"))
      (node (ref "U3") (pin "N13") (pinfunction "VCCO_14_N13") (pintype "power_in"))
      (node (ref "U3") (pin "N3") (pinfunction "VCCO_34_N3") (pintype "power_in"))
      (node (ref "U3") (pin "P16") (pinfunction "VCCO_14_P16") (pintype "power_in"))
      (node (ref "U3") (pin "P6") (pinfunction "VCCO_34_P6") (pintype "power_in"))
      (node (ref "U3") (pin "R9") (pinfunction "VCCO_0_R9") (pintype "power_in"))
      (node (ref "U3") (pin "T12") (pinfunction "VCCO_14_T12") (pintype "power_in"))
      (node (ref "U3") (pin "T2") (pinfunction "VCCO_34_T2") (pintype "power_in"))
      (node (ref "U3") (pin "U15") (pinfunction "VCCO_14_U15") (pintype "power_in"))
      (node (ref "U3") (pin "U5") (pinfunction "VCCO_34_U5") (pintype "power_in"))
      (node (ref "U3") (pin "V18") (pinfunction "VCCO_14_V18") (pintype "power_in"))
      (node (ref "U3") (pin "V8") (pinfunction "VCCO_34_V8") (pintype "power_in"))
    )
    (net (code "6") (name "XADC1V8") (class "Default")
      (node (ref "C93") (pin "1") (pinfunction "1_1") (pintype "passive"))
      (node (ref "C94") (pin "1") (pinfunction "1_1") (pintype "passive"))
      (node (ref "U3") (pin "H10") (pinfunction "VCCADC_0_H10") (pintype "power_in"))
    )
    (net (code "7") (name "XADCGND") (class "Default")
      (node (ref "C93") (pin "2") (pinfunction "2_2") (pintype "passive"))
      (node (ref "C94") (pin "2") (pinfunction "2_2") (pintype "passive"))
      (node (ref "U3") (pin "H9") (pinfunction "GNDADC_0_H9") (pintype "power_in"))
    )
  )
)
